# circuit.net
KiCad netlist of a schematic drawn in EasyEDA
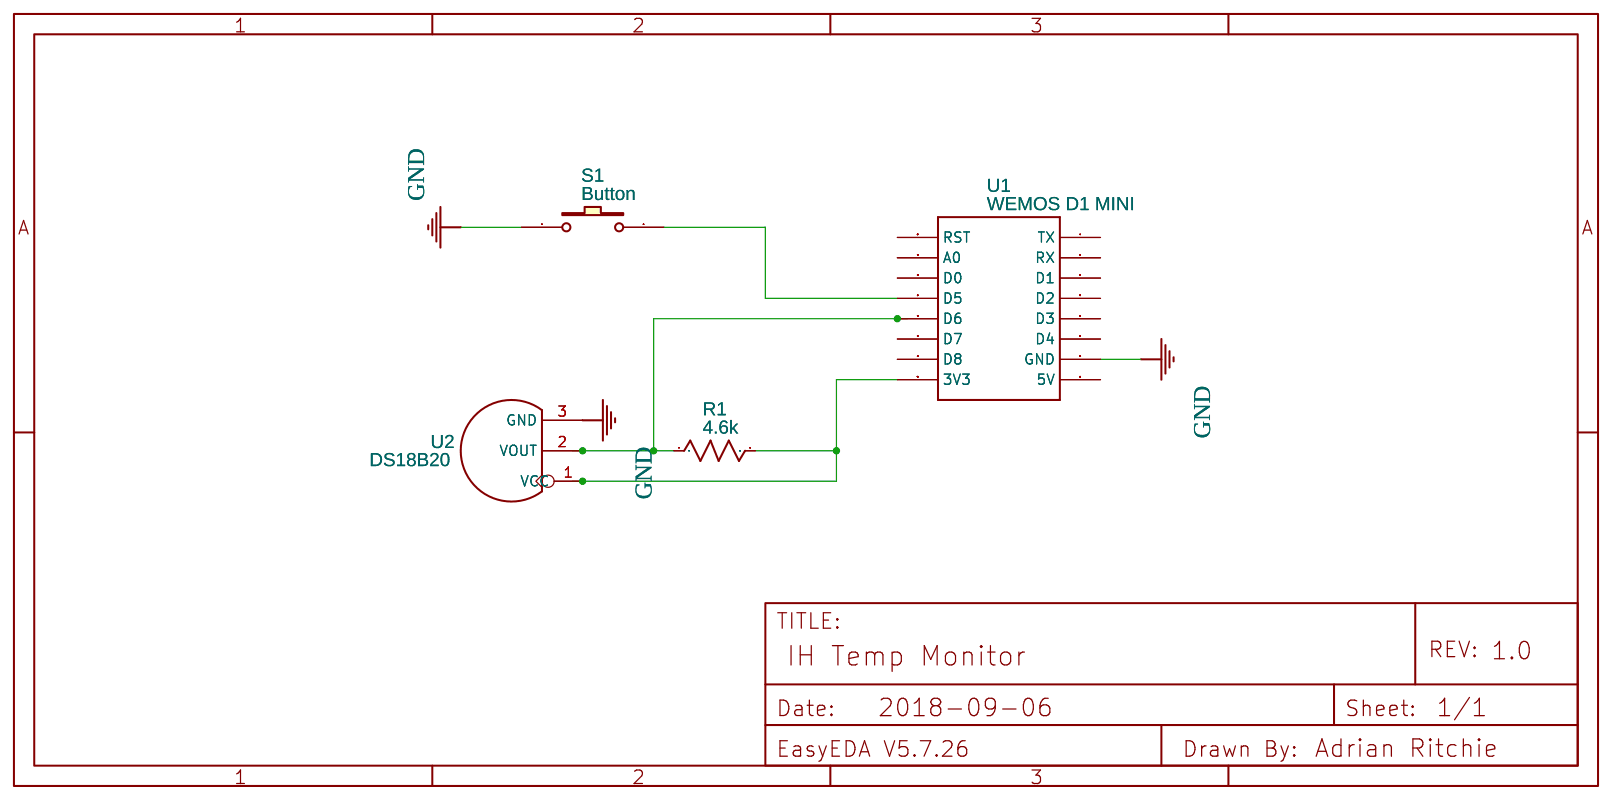
[diagram p0: schematic sheet]

(export (version "E")
  (design (tool "Eeschema 10.0.6"))
  (components
    (comp (ref "R1")
      (value "4.6k")
      (fields (field (name "BOM_Manufacturer Part") "?"))
      (libsource (lib "") (part "Res_AXIAL-0.3(1/8W)_US"))
    )
    (comp (ref "S1")
      (value "Button")
      (fields (field (name "BOM_Manufacturer Part") "?"))
      (libsource (lib "") (part "Unknown_380_320"))
    )
    (comp (ref "U1")
      (value "WEMOS D1 MINI")
      (fields (field (name "BOM_Manufacturer Part") "?"))
      (libsource (lib "") (part "Unknown_555_405"))
    )
    (comp (ref "U2")
      (value "DS18B20")
      (fields (field (name "BOM_Supplier Part") "314010014"))
      (libsource (lib "") (part "Unknown_350_430"))
    )
  )
  (nets
    (net (code "1") (name "GND") (class "Default")
      (node (ref "S1") (pin "1") (pintype "unspecified"))
      (node (ref "U1") (pin "GND") (pinfunction "GND_GND") (pintype "unspecified"))
      (node (ref "U2") (pin "3") (pinfunction "GND_3") (pintype "unspecified"))
    )
    (net (code "2") (name "Net-(S1-Pad2)") (class "Default")
      (node (ref "S1") (pin "2") (pintype "unspecified"))
      (node (ref "U1") (pin "D5") (pinfunction "D5_D5") (pintype "unspecified"))
    )
    (net (code "3") (name "Net-(U2-VCC)") (class "Default")
      (node (ref "R1") (pin "2") (pinfunction "2_2") (pintype "unspecified"))
      (node (ref "U1") (pin "3V3") (pinfunction "3V3_3V3") (pintype "unspecified"))
      (node (ref "U2") (pin "1") (pinfunction "VCC_1") (pintype "unspecified"))
    )
    (net (code "4") (name "Net-(U2-VOUT)") (class "Default")
      (node (ref "R1") (pin "1") (pinfunction "1_1") (pintype "unspecified"))
      (node (ref "U1") (pin "D6") (pinfunction "D6_D6") (pintype "unspecified"))
      (node (ref "U2") (pin "2") (pinfunction "VOUT_2") (pintype "unspecified"))
    )
    (net (code "5") (name "unconnected-(U1-Pad5V)") (class "Default")
      (node (ref "U1") (pin "5V") (pinfunction "5V_5V") (pintype "unspecified"))
    )
    (net (code "6") (name "unconnected-(U1-PadA0)") (class "Default")
      (node (ref "U1") (pin "A0") (pinfunction "A0_A0") (pintype "unspecified"))
    )
    (net (code "7") (name "unconnected-(U1-PadD0)") (class "Default")
      (node (ref "U1") (pin "D0") (pinfunction "D0_D0") (pintype "unspecified"))
    )
    (net (code "8") (name "unconnected-(U1-PadD1)") (class "Default")
      (node (ref "U1") (pin "D1") (pinfunction "D1_D1") (pintype "unspecified"))
    )
    (net (code "9") (name "unconnected-(U1-PadD2)") (class "Default")
      (node (ref "U1") (pin "D2") (pinfunction "D2_D2") (pintype "unspecified"))
    )
    (net (code "10") (name "unconnected-(U1-PadD3)") (class "Default")
      (node (ref "U1") (pin "D3") (pinfunction "D3_D3") (pintype "unspecified"))
    )
    (net (code "11") (name "unconnected-(U1-PadD4)") (class "Default")
      (node (ref "U1") (pin "D4") (pinfunction "D4_D4") (pintype "unspecified"))
    )
    (net (code "12") (name "unconnected-(U1-PadD7)") (class "Default")
      (node (ref "U1") (pin "D7") (pinfunction "D7_D7") (pintype "unspecified"))
    )
    (net (code "13") (name "unconnected-(U1-PadD8)") (class "Default")
      (node (ref "U1") (pin "D8") (pinfunction "D8_D8") (pintype "unspecified"))
    )
    (net (code "14") (name "unconnected-(U1-PadRST)") (class "Default")
      (node (ref "U1") (pin "RST") (pinfunction "RST_RST") (pintype "unspecified"))
    )
    (net (code "15") (name "unconnected-(U1-PadRX)") (class "Default")
      (node (ref "U1") (pin "RX") (pinfunction "RX_RX") (pintype "unspecified"))
    )
    (net (code "16") (name "unconnected-(U1-PadTX)") (class "Default")
      (node (ref "U1") (pin "TX") (pinfunction "TX_TX") (pintype "unspecified"))
    )
  )
)
